# thumb-4_0-schematic.net
KiCad netlist of a schematic drawn in EAGLE
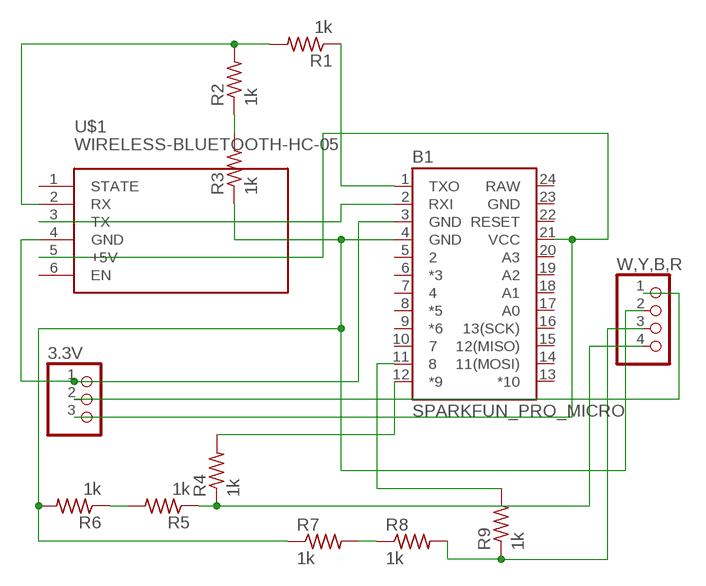
[diagram p0: schematic, sheet 1]

(export (version "E")
  (design (tool "Eeschema 10.0.6"))
  (components
    (comp (ref "3.3V")
      (value "PINHD-1X3")
      (footprint "eagle-import:1X03")
      (libsource (lib "eagle-import") (part "PINHD-1X3"))
    )
    (comp (ref "B1")
      (value "SPARKFUN_PRO_MICRO")
      (footprint "eagle-import:SPARKFUN_PRO_MICRO")
      (libsource (lib "eagle-import") (part "SPARKFUN_PRO_MICRO"))
    )
    (comp (ref "R1")
      (value "1k")
      (footprint "eagle-import:M1206")
      (libsource (lib "eagle-import") (part "resistor_R-US_M1206"))
    )
    (comp (ref "R2")
      (value "1k")
      (footprint "eagle-import:M1206")
      (libsource (lib "eagle-import") (part "resistor_R-US_M1206"))
    )
    (comp (ref "R3")
      (value "1k")
      (footprint "eagle-import:M1206")
      (libsource (lib "eagle-import") (part "resistor_R-US_M1206"))
    )
    (comp (ref "R4")
      (value "1k")
      (footprint "eagle-import:M1206")
      (libsource (lib "eagle-import") (part "resistor_R-US_M1206"))
    )
    (comp (ref "R5")
      (value "1k")
      (footprint "eagle-import:M1206")
      (libsource (lib "eagle-import") (part "resistor_R-US_M1206"))
    )
    (comp (ref "R6")
      (value "1k")
      (footprint "eagle-import:M1206")
      (libsource (lib "eagle-import") (part "resistor_R-US_M1206"))
    )
    (comp (ref "R7")
      (value "1k")
      (footprint "eagle-import:M1206")
      (libsource (lib "eagle-import") (part "R-US_M1206"))
    )
    (comp (ref "R8")
      (value "1k")
      (footprint "eagle-import:M1206")
      (libsource (lib "eagle-import") (part "R-US_M1206"))
    )
    (comp (ref "R9")
      (value "1k")
      (footprint "eagle-import:M1206")
      (libsource (lib "eagle-import") (part "R-US_M1206"))
    )
    (comp (ref "U$1")
      (value "WIRELESS-BLUETOOTH-HC-05")
      (footprint "eagle-import:WIRELESS-BLUETOOTH-HC-05")
      (libsource (lib "eagle-import") (part "WIRELESS-BLUETOOTH-HC-05"))
    )
    (comp (ref "W,Y,B,R")
      (value "PINHD-1X4")
      (footprint "eagle-import:1X04")
      (libsource (lib "eagle-import") (part "PINHD-1X4"))
    )
  )
  (nets
    (net (code "1") (name "/GND") (class "Default")
      (node (ref "B1") (pin "23") (pinfunction "GND_23") (pintype "power_in"))
    )
    (net (code "2") (name "/RAW") (class "Default")
      (node (ref "B1") (pin "24") (pinfunction "RAW_24") (pintype "power_in"))
    )
    (net (code "3") (name "Net-(3.3V-Pad2)") (class "Default")
      (node (ref "3.3V") (pin "2") (pinfunction "2_2") (pintype "passive"))
      (node (ref "W,Y,B,R") (pin "1") (pinfunction "1_1") (pintype "passive"))
    )
    (net (code "4") (name "Net-(B1-*9)") (class "Default")
      (node (ref "B1") (pin "12") (pinfunction "*9_12") (pintype "bidirectional"))
      (node (ref "R4") (pin "2") (pinfunction "2_2") (pintype "passive"))
    )
    (net (code "5") (name "Net-(B1-8)") (class "Default")
      (node (ref "B1") (pin "11") (pinfunction "8_11") (pintype "bidirectional"))
      (node (ref "R9") (pin "2") (pinfunction "2_2") (pintype "passive"))
    )
    (net (code "6") (name "Net-(B1-GND-Pad4)") (class "Default")
      (node (ref "B1") (pin "4") (pinfunction "GND_4") (pintype "power_in"))
      (node (ref "R3") (pin "1") (pinfunction "1_1") (pintype "passive"))
      (node (ref "R6") (pin "2") (pinfunction "2_2") (pintype "passive"))
      (node (ref "R7") (pin "1") (pinfunction "1_1") (pintype "passive"))
      (node (ref "W,Y,B,R") (pin "2") (pinfunction "2_2") (pintype "passive"))
    )
    (net (code "7") (name "Net-(B1-RXI)") (class "Default")
      (node (ref "B1") (pin "2") (pinfunction "RXI_2") (pintype "bidirectional"))
      (node (ref "U$1") (pin "3") (pinfunction "TX_3") (pintype "bidirectional"))
    )
    (net (code "8") (name "Net-(B1-TXO)") (class "Default")
      (node (ref "B1") (pin "1") (pinfunction "TXO_1") (pintype "bidirectional"))
      (node (ref "R1") (pin "1") (pinfunction "1_1") (pintype "passive"))
    )
    (net (code "9") (name "Net-(B1-VCC)") (class "Default")
      (node (ref "3.3V") (pin "3") (pinfunction "3_3") (pintype "passive"))
      (node (ref "B1") (pin "21") (pinfunction "VCC_21") (pintype "power_in"))
      (node (ref "U$1") (pin "5") (pinfunction "+5V_5") (pintype "power_in"))
    )
    (net (code "10") (name "Net-(R2-Pad1)") (class "Default")
      (node (ref "R2") (pin "1") (pinfunction "1_1") (pintype "passive"))
      (node (ref "R3") (pin "2") (pinfunction "2_2") (pintype "passive"))
    )
    (net (code "11") (name "Net-(R4-Pad1)") (class "Default")
      (node (ref "R4") (pin "1") (pinfunction "1_1") (pintype "passive"))
      (node (ref "R5") (pin "1") (pinfunction "1_1") (pintype "passive"))
      (node (ref "W,Y,B,R") (pin "4") (pinfunction "4_4") (pintype "passive"))
    )
    (net (code "12") (name "Net-(R5-Pad2)") (class "Default")
      (node (ref "R5") (pin "2") (pinfunction "2_2") (pintype "passive"))
      (node (ref "R6") (pin "1") (pinfunction "1_1") (pintype "passive"))
    )
    (net (code "13") (name "Net-(R7-Pad2)") (class "Default")
      (node (ref "R7") (pin "2") (pinfunction "2_2") (pintype "passive"))
      (node (ref "R8") (pin "1") (pinfunction "1_1") (pintype "passive"))
    )
    (net (code "14") (name "Net-(R8-Pad2)") (class "Default")
      (node (ref "R8") (pin "2") (pinfunction "2_2") (pintype "passive"))
      (node (ref "R9") (pin "1") (pinfunction "1_1") (pintype "passive"))
      (node (ref "W,Y,B,R") (pin "3") (pinfunction "3_3") (pintype "passive"))
    )
    (net (code "15") (name "Net-(U$1-GND)") (class "Default")
      (node (ref "3.3V") (pin "1") (pinfunction "1_1") (pintype "passive"))
      (node (ref "B1") (pin "3") (pinfunction "GND_3") (pintype "power_in"))
      (node (ref "U$1") (pin "4") (pinfunction "GND_4") (pintype "power_in"))
    )
    (net (code "16") (name "Net-(U$1-RX)") (class "Default")
      (node (ref "R1") (pin "2") (pinfunction "2_2") (pintype "passive"))
      (node (ref "R2") (pin "2") (pinfunction "2_2") (pintype "passive"))
      (node (ref "U$1") (pin "2") (pinfunction "RX_2") (pintype "bidirectional"))
    )
    (net (code "17") (name "unconnected-(B1-*3-Pad6)") (class "Default")
      (node (ref "B1") (pin "6") (pinfunction "*3_6") (pintype "bidirectional"))
    )
    (net (code "18") (name "unconnected-(B1-*5-Pad8)") (class "Default")
      (node (ref "B1") (pin "8") (pinfunction "*5_8") (pintype "bidirectional"))
    )
    (net (code "19") (name "unconnected-(B1-*6-Pad9)") (class "Default")
      (node (ref "B1") (pin "9") (pinfunction "*6_9") (pintype "bidirectional"))
    )
    (net (code "20") (name "unconnected-(B1-*10-Pad13)") (class "Default")
      (node (ref "B1") (pin "13") (pinfunction "*10_13") (pintype "bidirectional"))
    )
    (net (code "21") (name "unconnected-(B1-2-Pad5)") (class "Default")
      (node (ref "B1") (pin "5") (pinfunction "2_5") (pintype "bidirectional"))
    )
    (net (code "22") (name "unconnected-(B1-4-Pad7)") (class "Default")
      (node (ref "B1") (pin "7") (pinfunction "4_7") (pintype "bidirectional"))
    )
    (net (code "23") (name "unconnected-(B1-7-Pad10)") (class "Default")
      (node (ref "B1") (pin "10") (pinfunction "7_10") (pintype "bidirectional"))
    )
    (net (code "24") (name "unconnected-(B1-11(MOSI)-Pad14)") (class "Default")
      (node (ref "B1") (pin "14") (pinfunction "11(MOSI)_14") (pintype "bidirectional"))
    )
    (net (code "25") (name "unconnected-(B1-12(MISO)-Pad15)") (class "Default")
      (node (ref "B1") (pin "15") (pinfunction "12(MISO)_15") (pintype "bidirectional"))
    )
    (net (code "26") (name "unconnected-(B1-13(SCK)-Pad16)") (class "Default")
      (node (ref "B1") (pin "16") (pinfunction "13(SCK)_16") (pintype "bidirectional"))
    )
    (net (code "27") (name "unconnected-(B1-A0-Pad17)") (class "Default")
      (node (ref "B1") (pin "17") (pinfunction "A0_17") (pintype "bidirectional"))
    )
    (net (code "28") (name "unconnected-(B1-A1-Pad18)") (class "Default")
      (node (ref "B1") (pin "18") (pinfunction "A1_18") (pintype "bidirectional"))
    )
    (net (code "29") (name "unconnected-(B1-A2-Pad19)") (class "Default")
      (node (ref "B1") (pin "19") (pinfunction "A2_19") (pintype "bidirectional"))
    )
    (net (code "30") (name "unconnected-(B1-A3-Pad20)") (class "Default")
      (node (ref "B1") (pin "20") (pinfunction "A3_20") (pintype "bidirectional"))
    )
    (net (code "31") (name "unconnected-(B1-RESET-Pad22)") (class "Default")
      (node (ref "B1") (pin "22") (pinfunction "RESET_22") (pintype "bidirectional"))
    )
    (net (code "32") (name "unconnected-(U$1-EN-Pad6)") (class "Default")
      (node (ref "U$1") (pin "6") (pinfunction "EN_6") (pintype "bidirectional"))
    )
    (net (code "33") (name "unconnected-(U$1-STATE-Pad1)") (class "Default")
      (node (ref "U$1") (pin "1") (pinfunction "STATE_1") (pintype "bidirectional"))
    )
  )
)
